# MAGI_s7SegmentDisplay.net
KiCad netlist of a schematic drawn in Altium Designer
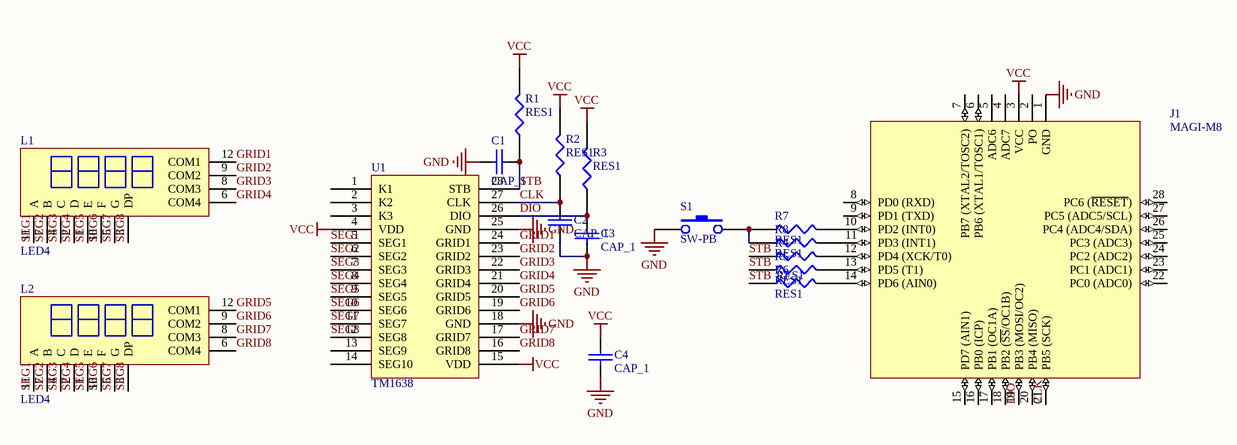
[diagram p0: MAGI's7SegmentDisplay.SchDoc]

(export (version "E")
  (design (tool "Eeschema 10.0.6"))
  (components
    (comp (ref "C1")
      (value "CAP_1")
      (footprint "6-0805_N")
      (description "Capacitor")
      (libsource (lib "电容器") (part "CAP_1"))
    )
    (comp (ref "C2")
      (value "CAP_1")
      (footprint "6-0805_N")
      (description "Capacitor")
      (libsource (lib "电容器") (part "CAP_1"))
    )
    (comp (ref "C3")
      (value "CAP_1")
      (footprint "6-0805_N")
      (description "Capacitor")
      (libsource (lib "电容器") (part "CAP_1"))
    )
    (comp (ref "C4")
      (value "CAP_1")
      (footprint "6-0805_N")
      (description "Capacitor")
      (libsource (lib "电容器") (part "CAP_1"))
    )
    (comp (ref "J1") (value "MAGI-M8") (footprint "MAGI-M8") (libsource (lib "MAGI-M8") (part "MAGI-M8")))
    (comp (ref "L1") (value "LED4") (footprint "0.36\"LED") (libsource (lib "04.数码管 LCD") (part "LED4")))
    (comp (ref "L2") (value "LED4") (footprint "0.36\"LED") (libsource (lib "04.数码管 LCD") (part "LED4")))
    (comp (ref "R1") (value "RES1") (footprint "6-0805_N") (libsource (lib "电阻器") (part "RES1")))
    (comp (ref "R2") (value "RES1") (footprint "6-0805_N") (libsource (lib "电阻器") (part "RES1")))
    (comp (ref "R3") (value "RES1") (footprint "6-0805_N") (libsource (lib "电阻器") (part "RES1")))
    (comp (ref "R4") (value "RES1") (footprint "1608[0603]") (libsource (lib "电阻器") (part "RES1")))
    (comp (ref "R5") (value "RES1") (footprint "1608[0603]") (libsource (lib "电阻器") (part "RES1")))
    (comp (ref "R6") (value "RES1") (footprint "1608[0603]") (libsource (lib "电阻器") (part "RES1")))
    (comp (ref "R7") (value "RES1") (footprint "1608[0603]") (libsource (lib "电阻器") (part "RES1")))
    (comp (ref "R8") (value "RES1") (footprint "1608[0603]") (libsource (lib "电阻器") (part "RES1")))
    (comp (ref "S1") (value "SW-PB") (footprint "SW-1-SMD") (libsource (lib "手动开关") (part "SW-PB")))
    (comp (ref "U1") (value "TM1638") (footprint "TM1638") (libsource (lib "LEDDriver") (part "TM1638")))
  )
  (nets
    (net (code "1") (name "/CLK") (class "Default")
      (node (ref "C2") (pin "2") (pinfunction "2_2") (pintype "passive"))
      (node (ref "J1") (pin "21") (pinfunction "PB5_(SCK)_21") (pintype "bidirectional"))
      (node (ref "R2") (pin "1") (pinfunction "1_1") (pintype "passive"))
      (node (ref "U1") (pin "27") (pinfunction "CLK_27") (pintype "passive"))
    )
    (net (code "2") (name "/DIO") (class "Default")
      (node (ref "C3") (pin "2") (pinfunction "2_2") (pintype "passive"))
      (node (ref "J1") (pin "19") (pinfunction "PB3_(MOSI/OC2)_19") (pintype "bidirectional"))
      (node (ref "R3") (pin "1") (pinfunction "1_1") (pintype "passive"))
      (node (ref "U1") (pin "26") (pinfunction "DIO_26") (pintype "passive"))
    )
    (net (code "3") (name "/GRID1") (class "Default")
      (node (ref "L1") (pin "12") (pinfunction "COM1_12") (pintype "passive"))
      (node (ref "U1") (pin "24") (pinfunction "GRID1_24") (pintype "passive"))
    )
    (net (code "4") (name "/GRID2") (class "Default")
      (node (ref "L1") (pin "9") (pinfunction "COM2_9") (pintype "passive"))
      (node (ref "U1") (pin "23") (pinfunction "GRID2_23") (pintype "passive"))
    )
    (net (code "5") (name "/GRID3") (class "Default")
      (node (ref "L1") (pin "8") (pinfunction "COM3_8") (pintype "passive"))
      (node (ref "U1") (pin "22") (pinfunction "GRID3_22") (pintype "passive"))
    )
    (net (code "6") (name "/GRID4") (class "Default")
      (node (ref "L1") (pin "6") (pinfunction "COM4_6") (pintype "passive"))
      (node (ref "U1") (pin "21") (pinfunction "GRID4_21") (pintype "passive"))
    )
    (net (code "7") (name "/GRID5") (class "Default")
      (node (ref "L2") (pin "12") (pinfunction "COM1_12") (pintype "passive"))
      (node (ref "U1") (pin "20") (pinfunction "GRID5_20") (pintype "passive"))
    )
    (net (code "8") (name "/GRID6") (class "Default")
      (node (ref "L2") (pin "9") (pinfunction "COM2_9") (pintype "passive"))
      (node (ref "U1") (pin "19") (pinfunction "GRID6_19") (pintype "passive"))
    )
    (net (code "9") (name "/GRID7") (class "Default")
      (node (ref "L2") (pin "8") (pinfunction "COM3_8") (pintype "passive"))
      (node (ref "U1") (pin "17") (pinfunction "GRID7_17") (pintype "passive"))
    )
    (net (code "10") (name "/GRID8") (class "Default")
      (node (ref "L2") (pin "6") (pinfunction "COM4_6") (pintype "passive"))
      (node (ref "U1") (pin "16") (pinfunction "GRID8_16") (pintype "passive"))
    )
    (net (code "11") (name "/SEG1") (class "Default")
      (node (ref "L1") (pin "11") (pinfunction "A_11") (pintype "passive"))
      (node (ref "L2") (pin "11") (pinfunction "A_11") (pintype "passive"))
      (node (ref "U1") (pin "5") (pinfunction "SEG1_5") (pintype "passive"))
    )
    (net (code "12") (name "/SEG2") (class "Default")
      (node (ref "L1") (pin "7") (pinfunction "B_7") (pintype "passive"))
      (node (ref "L2") (pin "7") (pinfunction "B_7") (pintype "passive"))
      (node (ref "U1") (pin "6") (pinfunction "SEG2_6") (pintype "passive"))
    )
    (net (code "13") (name "/SEG3") (class "Default")
      (node (ref "L1") (pin "4") (pinfunction "C_4") (pintype "passive"))
      (node (ref "L2") (pin "4") (pinfunction "C_4") (pintype "passive"))
      (node (ref "U1") (pin "7") (pinfunction "SEG3_7") (pintype "passive"))
    )
    (net (code "14") (name "/SEG4") (class "Default")
      (node (ref "L1") (pin "2") (pinfunction "D_2") (pintype "passive"))
      (node (ref "L2") (pin "2") (pinfunction "D_2") (pintype "passive"))
      (node (ref "U1") (pin "8") (pinfunction "SEG4_8") (pintype "passive"))
    )
    (net (code "15") (name "/SEG5") (class "Default")
      (node (ref "L1") (pin "1") (pinfunction "E_1") (pintype "passive"))
      (node (ref "L2") (pin "1") (pinfunction "E_1") (pintype "passive"))
      (node (ref "U1") (pin "9") (pinfunction "SEG5_9") (pintype "passive"))
    )
    (net (code "16") (name "/SEG6") (class "Default")
      (node (ref "L1") (pin "10") (pinfunction "F_10") (pintype "passive"))
      (node (ref "L2") (pin "10") (pinfunction "F_10") (pintype "passive"))
      (node (ref "U1") (pin "10") (pinfunction "SEG6_10") (pintype "passive"))
    )
    (net (code "17") (name "/SEG7") (class "Default")
      (node (ref "L1") (pin "5") (pinfunction "G_5") (pintype "passive"))
      (node (ref "L2") (pin "5") (pinfunction "G_5") (pintype "passive"))
      (node (ref "U1") (pin "11") (pinfunction "SEG7_11") (pintype "passive"))
    )
    (net (code "18") (name "/SEG8") (class "Default")
      (node (ref "L1") (pin "3") (pinfunction "DP_3") (pintype "passive"))
      (node (ref "L2") (pin "3") (pinfunction "DP_3") (pintype "passive"))
      (node (ref "U1") (pin "12") (pinfunction "SEG8_12") (pintype "passive"))
    )
    (net (code "19") (name "/STB") (class "Default")
      (node (ref "C1") (pin "1") (pinfunction "1_1") (pintype "passive"))
      (node (ref "R1") (pin "1") (pinfunction "1_1") (pintype "passive"))
      (node (ref "R4") (pin "1") (pinfunction "1_1") (pintype "passive"))
      (node (ref "R5") (pin "1") (pinfunction "1_1") (pintype "passive"))
      (node (ref "R6") (pin "1") (pinfunction "1_1") (pintype "passive"))
      (node (ref "U1") (pin "28") (pinfunction "STB_28") (pintype "passive"))
    )
    (net (code "20") (name "GND") (class "Default")
      (node (ref "C1") (pin "2") (pinfunction "2_2") (pintype "passive"))
      (node (ref "C2") (pin "1") (pinfunction "1_1") (pintype "passive"))
      (node (ref "C3") (pin "1") (pinfunction "1_1") (pintype "passive"))
      (node (ref "C4") (pin "2") (pinfunction "2_2") (pintype "passive"))
      (node (ref "J1") (pin "1") (pinfunction "GND_1") (pintype "power_in"))
      (node (ref "S1") (pin "1") (pinfunction "1_1") (pintype "passive"))
      (node (ref "U1") (pin "18") (pinfunction "GND_18") (pintype "passive"))
      (node (ref "U1") (pin "25") (pinfunction "GND_25") (pintype "passive"))
    )
    (net (code "21") (name "Net-(J1-PD2_(INT0))") (class "Default")
      (node (ref "J1") (pin "10") (pinfunction "PD2_(INT0)_10") (pintype "bidirectional"))
      (node (ref "R7") (pin "2") (pinfunction "2_2") (pintype "passive"))
    )
    (net (code "22") (name "Net-(J1-PD3_(INT1))") (class "Default")
      (node (ref "J1") (pin "11") (pinfunction "PD3_(INT1)_11") (pintype "bidirectional"))
      (node (ref "R8") (pin "2") (pinfunction "2_2") (pintype "passive"))
    )
    (net (code "23") (name "Net-(J1-PD4_(XCK{slash}T0))") (class "Default")
      (node (ref "J1") (pin "12") (pinfunction "PD4_(XCK/T0)_12") (pintype "bidirectional"))
      (node (ref "R4") (pin "2") (pinfunction "2_2") (pintype "passive"))
    )
    (net (code "24") (name "Net-(J1-PD5_(T1))") (class "Default")
      (node (ref "J1") (pin "13") (pinfunction "PD5_(T1)_13") (pintype "bidirectional"))
      (node (ref "R5") (pin "2") (pinfunction "2_2") (pintype "passive"))
    )
    (net (code "25") (name "Net-(J1-PD6_(AIN0))") (class "Default")
      (node (ref "J1") (pin "14") (pinfunction "PD6_(AIN0)_14") (pintype "bidirectional"))
      (node (ref "R6") (pin "2") (pinfunction "2_2") (pintype "passive"))
    )
    (net (code "26") (name "Net-(R7-Pad1)") (class "Default")
      (node (ref "R7") (pin "1") (pinfunction "1_1") (pintype "passive"))
      (node (ref "R8") (pin "1") (pinfunction "1_1") (pintype "passive"))
      (node (ref "S1") (pin "2") (pinfunction "2_2") (pintype "passive"))
    )
    (net (code "27") (name "VCC") (class "Default")
      (node (ref "C4") (pin "1") (pinfunction "1_1") (pintype "passive"))
      (node (ref "J1") (pin "3") (pinfunction "VCC_3") (pintype "power_in"))
      (node (ref "R1") (pin "2") (pinfunction "2_2") (pintype "passive"))
      (node (ref "R2") (pin "2") (pinfunction "2_2") (pintype "passive"))
      (node (ref "R3") (pin "2") (pinfunction "2_2") (pintype "passive"))
      (node (ref "U1") (pin "15") (pinfunction "VDD_15") (pintype "passive"))
      (node (ref "U1") (pin "4") (pinfunction "VDD_4") (pintype "passive"))
    )
    (net (code "28") (name "unconnected-(J1-ADC6-Pad5)") (class "Default")
      (node (ref "J1") (pin "5") (pinfunction "ADC6_5") (pintype "passive"))
    )
    (net (code "29") (name "unconnected-(J1-ADC7-Pad4)") (class "Default")
      (node (ref "J1") (pin "4") (pinfunction "ADC7_4") (pintype "passive"))
    )
    (net (code "30") (name "unconnected-(J1-PB0_(ICP)-Pad16)") (class "Default")
      (node (ref "J1") (pin "16") (pinfunction "PB0_(ICP)_16") (pintype "bidirectional"))
    )
    (net (code "31") (name "unconnected-(J1-PB1_(OC1A)-Pad17)") (class "Default")
      (node (ref "J1") (pin "17") (pinfunction "PB1_(OC1A)_17") (pintype "bidirectional"))
    )
    (net (code "32") (name "unconnected-(J1-PB2_(~{SS}{slash}OC1B)-Pad18)") (class "Default")
      (node (ref "J1") (pin "18") (pinfunction "PB2_(~{SS}/OC1B)_18") (pintype "bidirectional"))
    )
    (net (code "33") (name "unconnected-(J1-PB4_(MISO)-Pad20)") (class "Default")
      (node (ref "J1") (pin "20") (pinfunction "PB4_(MISO)_20") (pintype "bidirectional"))
    )
    (net (code "34") (name "unconnected-(J1-PB6_(XTAL1{slash}TOSC1)-Pad6)") (class "Default")
      (node (ref "J1") (pin "6") (pinfunction "PB6_(XTAL1/TOSC1)_6") (pintype "bidirectional"))
    )
    (net (code "35") (name "unconnected-(J1-PB7_(XTAL2{slash}TOSC2)-Pad7)") (class "Default")
      (node (ref "J1") (pin "7") (pinfunction "PB7_(XTAL2/TOSC2)_7") (pintype "bidirectional"))
    )
    (net (code "36") (name "unconnected-(J1-PC0_(ADC0)-Pad22)") (class "Default")
      (node (ref "J1") (pin "22") (pinfunction "PC0_(ADC0)_22") (pintype "bidirectional"))
    )
    (net (code "37") (name "unconnected-(J1-PC1_(ADC1)-Pad23)") (class "Default")
      (node (ref "J1") (pin "23") (pinfunction "PC1_(ADC1)_23") (pintype "bidirectional"))
    )
    (net (code "38") (name "unconnected-(J1-PC2_(ADC2)-Pad24)") (class "Default")
      (node (ref "J1") (pin "24") (pinfunction "PC2_(ADC2)_24") (pintype "bidirectional"))
    )
    (net (code "39") (name "unconnected-(J1-PC3_(ADC3)-Pad25)") (class "Default")
      (node (ref "J1") (pin "25") (pinfunction "PC3_(ADC3)_25") (pintype "bidirectional"))
    )
    (net (code "40") (name "unconnected-(J1-PC4_(ADC4{slash}SDA)-Pad26)") (class "Default")
      (node (ref "J1") (pin "26") (pinfunction "PC4_(ADC4/SDA)_26") (pintype "bidirectional"))
    )
    (net (code "41") (name "unconnected-(J1-PC5_(ADC5{slash}SCL)-Pad27)") (class "Default")
      (node (ref "J1") (pin "27") (pinfunction "PC5_(ADC5/SCL)_27") (pintype "bidirectional"))
    )
    (net (code "42") (name "unconnected-(J1-PC6_(~{RESET})-Pad28)") (class "Default")
      (node (ref "J1") (pin "28") (pinfunction "PC6_(~{RESET})_28") (pintype "bidirectional"))
    )
    (net (code "43") (name "unconnected-(J1-PD0_(RXD)-Pad8)") (class "Default")
      (node (ref "J1") (pin "8") (pinfunction "PD0_(RXD)_8") (pintype "bidirectional"))
    )
    (net (code "44") (name "unconnected-(J1-PD1_(TXD)-Pad9)") (class "Default")
      (node (ref "J1") (pin "9") (pinfunction "PD1_(TXD)_9") (pintype "bidirectional"))
    )
    (net (code "45") (name "unconnected-(J1-PD7_(AIN1)-Pad15)") (class "Default")
      (node (ref "J1") (pin "15") (pinfunction "PD7_(AIN1)_15") (pintype "bidirectional"))
    )
    (net (code "46") (name "unconnected-(J1-PO-Pad2)") (class "Default")
      (node (ref "J1") (pin "2") (pinfunction "PO_2") (pintype "power_in"))
    )
    (net (code "47") (name "unconnected-(U1-K1-Pad1)") (class "Default")
      (node (ref "U1") (pin "1") (pinfunction "K1_1") (pintype "passive"))
    )
    (net (code "48") (name "unconnected-(U1-K2-Pad2)") (class "Default")
      (node (ref "U1") (pin "2") (pinfunction "K2_2") (pintype "passive"))
    )
    (net (code "49") (name "unconnected-(U1-K3-Pad3)") (class "Default")
      (node (ref "U1") (pin "3") (pinfunction "K3_3") (pintype "passive"))
    )
    (net (code "50") (name "unconnected-(U1-SEG9-Pad13)") (class "Default")
      (node (ref "U1") (pin "13") (pinfunction "SEG9_13") (pintype "passive"))
    )
    (net (code "51") (name "unconnected-(U1-SEG10-Pad14)") (class "Default")
      (node (ref "U1") (pin "14") (pinfunction "SEG10_14") (pintype "passive"))
    )
  )
)
